# Adafruit-MAX17048-STEMMA.net
KiCad netlist of a schematic drawn in EAGLE
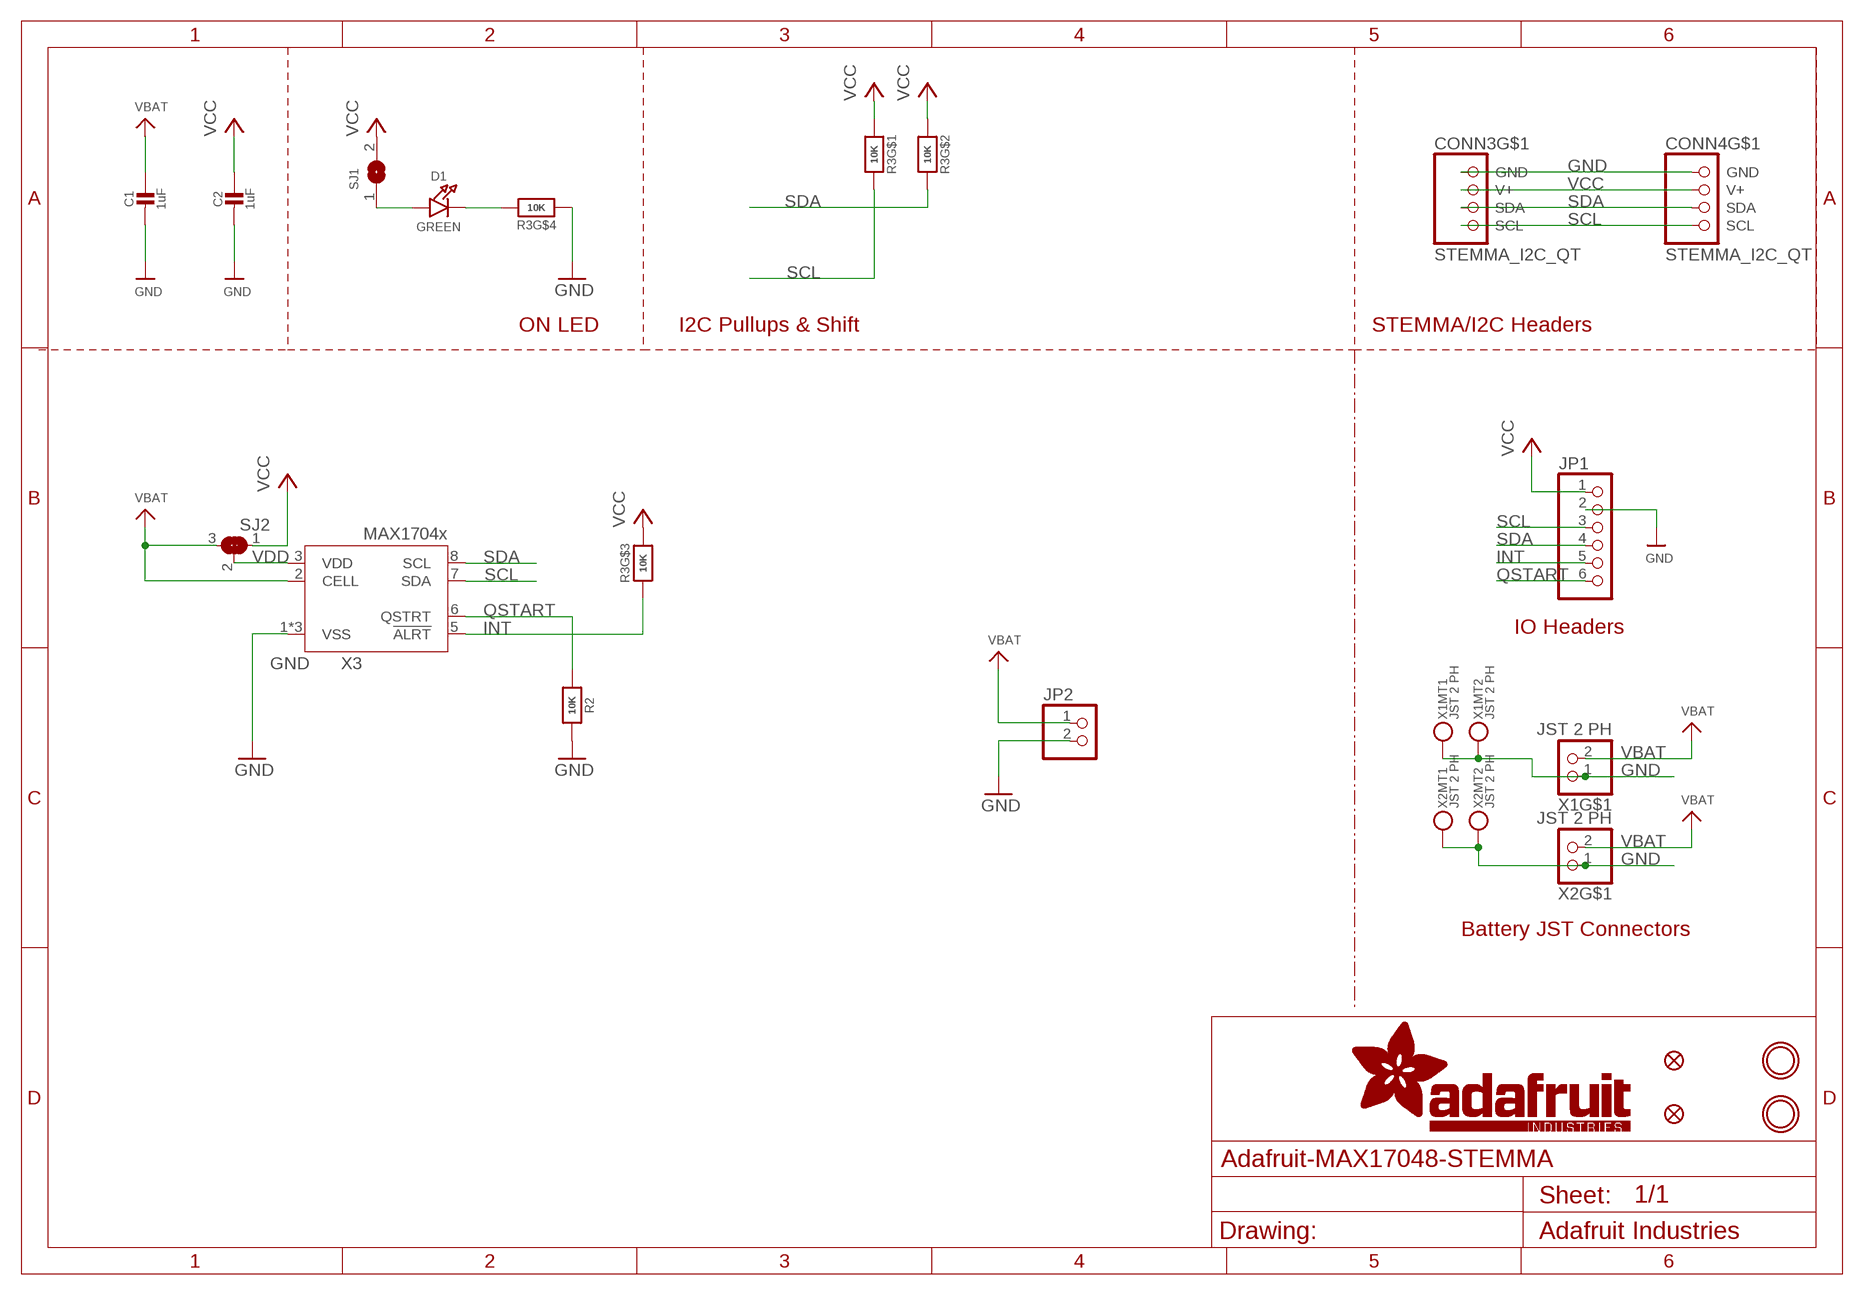
[diagram p0: schematic, sheet 1]

(export (version "E")
  (design (tool "Eeschema 10.0.6"))
  (components
    (comp (ref "C1")
      (value "1uF")
      (footprint "eagle-import:0603-NO")
      (libsource (lib "eagle-import") (part "CAP_CERAMIC0603_NO"))
    )
    (comp (ref "C2")
      (value "1uF")
      (footprint "eagle-import:0603-NO")
      (libsource (lib "eagle-import") (part "CAP_CERAMIC0603_NO"))
    )
    (comp (ref "CONN3")
      (value "STEMMA_I2C_QT")
      (footprint "eagle-import:JST_SH4")
      (libsource (lib "eagle-import") (part "STEMMA_I2C_QT"))
    )
    (comp (ref "CONN4")
      (value "STEMMA_I2C_QT")
      (footprint "eagle-import:JST_SH4")
      (libsource (lib "eagle-import") (part "STEMMA_I2C_QT"))
    )
    (comp (ref "D1")
      (value "GREEN")
      (footprint "eagle-import:CHIPLED_0603_NOOUTLINE")
      (libsource (lib "eagle-import") (part "LED0603_NOOUTLINE"))
    )
    (comp (ref "FID3")
      (value "FIDUCIAL_1MM")
      (footprint "eagle-import:FIDUCIAL_1MM")
      (libsource (lib "eagle-import") (part "FIDUCIAL_1MM"))
    )
    (comp (ref "FID4")
      (value "FIDUCIAL_1MM")
      (footprint "eagle-import:FIDUCIAL_1MM")
      (libsource (lib "eagle-import") (part "FIDUCIAL_1MM"))
    )
    (comp (ref "JP1")
      (value "HEADER-1X670MIL")
      (footprint "eagle-import:1X06_ROUND_70")
      (libsource (lib "eagle-import") (part "HEADER-1X670MIL"))
    )
    (comp (ref "JP2")
      (value "HEADER-1X2ROUND")
      (footprint "eagle-import:1X02_ROUND")
      (libsource (lib "eagle-import") (part "HEADER-1X2ROUND"))
    )
    (comp (ref "R2")
      (value "10K")
      (footprint "eagle-import:0603-NO")
      (libsource (lib "eagle-import") (part "RESISTOR_0603_NOOUT"))
    )
    (comp (ref "R3")
      (value "10K")
      (footprint "eagle-import:RESPACK_4X0603")
      (libsource (lib "eagle-import") (part "RESISTOR_4PACK"))
    )
    (comp (ref "SJ1")
      (value "SOLDERJUMPERCLOSED")
      (footprint "eagle-import:SOLDERJUMPER_CLOSEDWIRE")
      (libsource (lib "eagle-import") (part "SOLDERJUMPERCLOSED"))
    )
    (comp (ref "SJ2")
      (value "SOLDERJUMPER_2WAY")
      (footprint "eagle-import:SOLDERJUMPER_2WAY_OPEN_NOPASTE")
      (libsource (lib "eagle-import") (part "SOLDERJUMPER_2WAY"))
    )
    (comp (ref "U$19")
      (value "MOUNTINGHOLE2.5")
      (footprint "eagle-import:MOUNTINGHOLE_2.5_PLATED")
      (libsource (lib "eagle-import") (part "MOUNTINGHOLE2.5"))
    )
    (comp (ref "U$21")
      (value "MOUNTINGHOLE2.5")
      (footprint "eagle-import:MOUNTINGHOLE_2.5_PLATED")
      (libsource (lib "eagle-import") (part "MOUNTINGHOLE2.5"))
    )
    (comp (ref "X1")
      (value "JST 2 PH")
      (footprint "eagle-import:JSTPH2_BATT")
      (libsource (lib "eagle-import") (part "CON_JST_PH_2PIN_MT_BATT"))
    )
    (comp (ref "X2")
      (value "JST 2 PH")
      (footprint "eagle-import:JSTPH2_BATT")
      (libsource (lib "eagle-import") (part "CON_JST_PH_2PIN_MT_BATT"))
    )
    (comp (ref "X3")
      (value "MAX17048/T")
      (footprint "eagle-import:TDFN8_2X2MM")
      (libsource (lib "eagle-import") (part "MAX17048/T"))
    )
  )
  (nets
    (net (code "1") (name "/INT") (class "Default")
      (node (ref "JP1") (pin "5") (pinfunction "5_5") (pintype "passive"))
      (node (ref "R3") (pin "3") (pinfunction "1_3") (pintype "passive"))
      (node (ref "X3") (pin "5") (pinfunction "~{ALRT}_5") (pintype "output"))
    )
    (net (code "2") (name "/QSTART") (class "Default")
      (node (ref "JP1") (pin "6") (pinfunction "6_6") (pintype "passive"))
      (node (ref "R2") (pin "1") (pinfunction "1_1") (pintype "passive"))
      (node (ref "X3") (pin "6") (pinfunction "QSTRT_6") (pintype "input"))
    )
    (net (code "3") (name "/SCL") (class "Default")
      (node (ref "CONN3") (pin "4") (pinfunction "SCL_4") (pintype "passive"))
      (node (ref "CONN4") (pin "4") (pinfunction "SCL_4") (pintype "passive"))
      (node (ref "JP1") (pin "3") (pinfunction "3_3") (pintype "passive"))
      (node (ref "R3") (pin "8") (pinfunction "2_8") (pintype "passive"))
      (node (ref "X3") (pin "7") (pinfunction "SDA_7") (pintype "bidirectional"))
    )
    (net (code "4") (name "/SDA") (class "Default")
      (node (ref "CONN3") (pin "3") (pinfunction "SDA_3") (pintype "passive"))
      (node (ref "CONN4") (pin "3") (pinfunction "SDA_3") (pintype "passive"))
      (node (ref "JP1") (pin "4") (pinfunction "4_4") (pintype "passive"))
      (node (ref "R3") (pin "7") (pinfunction "2_7") (pintype "passive"))
      (node (ref "X3") (pin "8") (pinfunction "SCL_8") (pintype "bidirectional"))
    )
    (net (code "5") (name "/VDD") (class "Default")
      (node (ref "SJ2") (pin "2") (pinfunction "2_2") (pintype "passive"))
      (node (ref "X3") (pin "3") (pinfunction "VDD_3") (pintype "power_in"))
    )
    (net (code "6") (name "GND") (class "Default")
      (node (ref "C1") (pin "2") (pinfunction "2_2") (pintype "passive"))
      (node (ref "C2") (pin "2") (pinfunction "2_2") (pintype "passive"))
      (node (ref "CONN3") (pin "1") (pinfunction "GND_1") (pintype "passive"))
      (node (ref "CONN4") (pin "1") (pinfunction "GND_1") (pintype "passive"))
      (node (ref "JP1") (pin "2") (pinfunction "2_2") (pintype "passive"))
      (node (ref "JP2") (pin "2") (pinfunction "2_2") (pintype "passive"))
      (node (ref "R2") (pin "2") (pinfunction "2_2") (pintype "passive"))
      (node (ref "R3") (pin "4") (pinfunction "1_4") (pintype "passive"))
      (node (ref "X1") (pin "1") (pinfunction "1_1") (pintype "passive"))
      (node (ref "X1") (pin "NC1") (pinfunction "P$1_NC1") (pintype "bidirectional"))
      (node (ref "X1") (pin "NC2") (pinfunction "P$1_NC2") (pintype "bidirectional"))
      (node (ref "X2") (pin "1") (pinfunction "1_1") (pintype "passive"))
      (node (ref "X2") (pin "NC1") (pinfunction "P$1_NC1") (pintype "bidirectional"))
      (node (ref "X2") (pin "NC2") (pinfunction "P$1_NC2") (pintype "bidirectional"))
      (node (ref "X3") (pin "1") (pinfunction "VSS_1") (pintype "power_in"))
      (node (ref "X3") (pin "4") (pinfunction "VSS_4") (pintype "power_in"))
      (node (ref "X3") (pin "THERMAL") (pinfunction "VSS_THERMAL") (pintype "power_in"))
    )
    (net (code "7") (name "Net-(D1-PadA)") (class "Default")
      (node (ref "D1") (pin "A") (pinfunction "A_A") (pintype "passive"))
      (node (ref "SJ1") (pin "1") (pinfunction "1_1") (pintype "passive"))
    )
    (net (code "8") (name "Net-(R3D-2)") (class "Default")
      (node (ref "D1") (pin "C") (pinfunction "C_C") (pintype "passive"))
      (node (ref "R3") (pin "5") (pinfunction "2_5") (pintype "passive"))
    )
    (net (code "9") (name "VBAT") (class "Default")
      (node (ref "C1") (pin "1") (pinfunction "1_1") (pintype "passive"))
      (node (ref "JP2") (pin "1") (pinfunction "1_1") (pintype "passive"))
      (node (ref "SJ2") (pin "3") (pinfunction "3_3") (pintype "passive"))
      (node (ref "X1") (pin "2") (pinfunction "2_2") (pintype "passive"))
      (node (ref "X2") (pin "2") (pinfunction "2_2") (pintype "passive"))
      (node (ref "X3") (pin "2") (pinfunction "CELL_2") (pintype "power_in"))
    )
    (net (code "10") (name "VCC") (class "Default")
      (node (ref "C2") (pin "1") (pinfunction "1_1") (pintype "passive"))
      (node (ref "CONN3") (pin "2") (pinfunction "V+_2") (pintype "passive"))
      (node (ref "CONN4") (pin "2") (pinfunction "V+_2") (pintype "passive"))
      (node (ref "JP1") (pin "1") (pinfunction "1_1") (pintype "passive"))
      (node (ref "R3") (pin "1") (pinfunction "1_1") (pintype "passive"))
      (node (ref "R3") (pin "2") (pinfunction "1_2") (pintype "passive"))
      (node (ref "R3") (pin "6") (pinfunction "2_6") (pintype "passive"))
      (node (ref "SJ1") (pin "2") (pinfunction "2_2") (pintype "passive"))
      (node (ref "SJ2") (pin "1") (pinfunction "1_1") (pintype "passive"))
    )
  )
)
